# UmnitsaControl.net
KiCad netlist of a schematic drawn in EAGLE
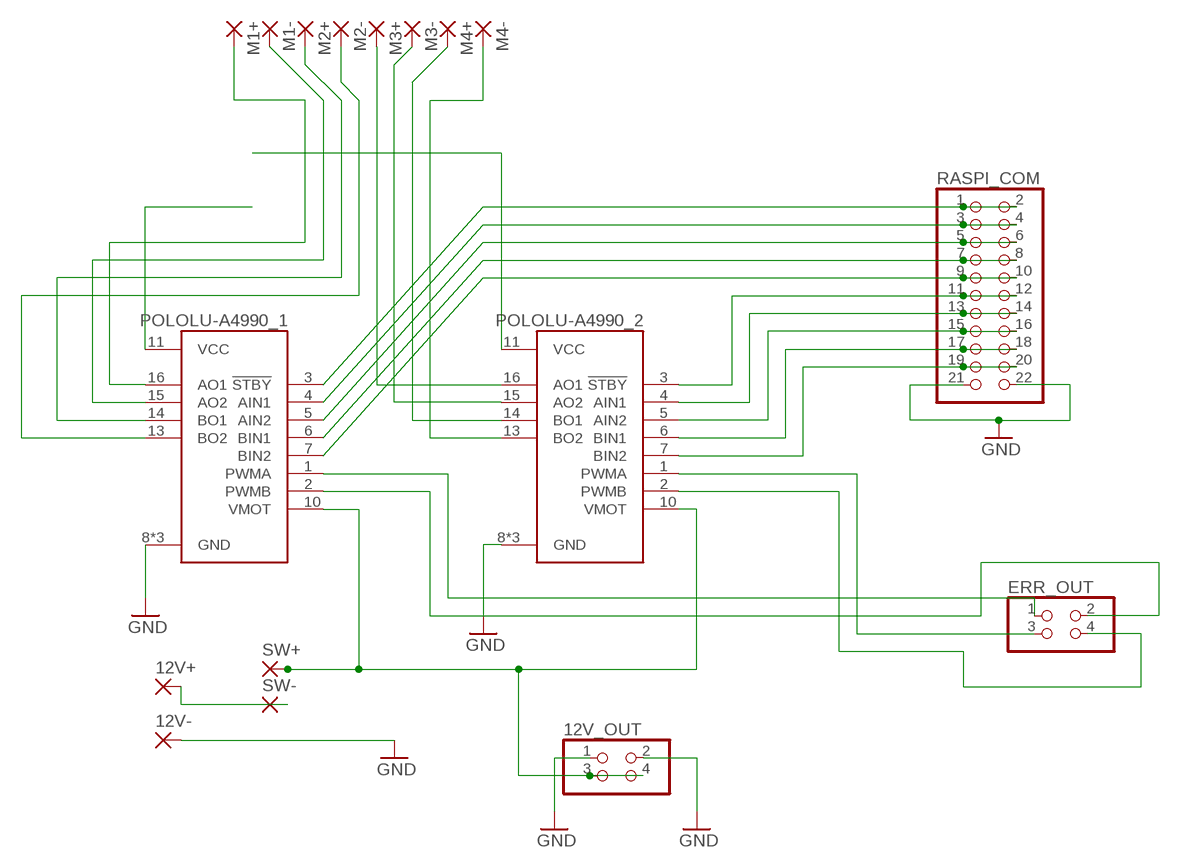
[diagram p0: schematic, sheet 1]

(export (version "E")
  (design (tool "Eeschema 10.0.6"))
  (components
    (comp (ref "12V+")
      (value "3,81/1,4")
      (footprint "eagle-import:3,81_1,4")
      (libsource (lib "eagle-import") (part "3,81/1,4"))
    )
    (comp (ref "12V-")
      (value "3,81/1,4")
      (footprint "eagle-import:3,81_1,4")
      (libsource (lib "eagle-import") (part "3,81/1,4"))
    )
    (comp (ref "12V_OUT")
      (value "PINHD-2X2")
      (footprint "eagle-import:2X02")
      (libsource (lib "eagle-import") (part "PINHD-2X2"))
    )
    (comp (ref "ERR_OUT")
      (value "PINHD-2X2")
      (footprint "eagle-import:2X02")
      (libsource (lib "eagle-import") (part "PINHD-2X2"))
    )
    (comp (ref "M1+")
      (value "3,81/1,4")
      (footprint "eagle-import:3,81_1,4")
      (libsource (lib "eagle-import") (part "3,81/1,4"))
    )
    (comp (ref "M1-")
      (value "3,81/1,4")
      (footprint "eagle-import:3,81_1,4")
      (libsource (lib "eagle-import") (part "3,81/1,4"))
    )
    (comp (ref "M2+")
      (value "3,81/1,4")
      (footprint "eagle-import:3,81_1,4")
      (libsource (lib "eagle-import") (part "3,81/1,4"))
    )
    (comp (ref "M2-")
      (value "3,81/1,4")
      (footprint "eagle-import:3,81_1,4")
      (libsource (lib "eagle-import") (part "3,81/1,4"))
    )
    (comp (ref "M3+")
      (value "3,81/1,4")
      (footprint "eagle-import:3,81_1,4")
      (libsource (lib "eagle-import") (part "3,81/1,4"))
    )
    (comp (ref "M3-")
      (value "3,81/1,4")
      (footprint "eagle-import:3,81_1,4")
      (libsource (lib "eagle-import") (part "3,81/1,4"))
    )
    (comp (ref "M4+")
      (value "3,81/1,4")
      (footprint "eagle-import:3,81_1,4")
      (libsource (lib "eagle-import") (part "3,81/1,4"))
    )
    (comp (ref "M4-")
      (value "3,81/1,4")
      (footprint "eagle-import:3,81_1,4")
      (libsource (lib "eagle-import") (part "3,81/1,4"))
    )
    (comp (ref "POLOLU-A4990_1")
      (value "POLOLU-713")
      (footprint "eagle-import:SHIELD_POLOLU-713")
      (fields (field (name "MF") "Pololu"))
      (libsource (lib "eagle-import") (part "POLOLU-713"))
    )
    (comp (ref "POLOLU-A4990_2")
      (value "POLOLU-713")
      (footprint "eagle-import:SHIELD_POLOLU-713")
      (fields (field (name "MF") "Pololu"))
      (libsource (lib "eagle-import") (part "POLOLU-713"))
    )
    (comp (ref "RASPI_COM")
      (value "PINHD-2X11")
      (footprint "eagle-import:2X11")
      (libsource (lib "eagle-import") (part "PINHD-2X11"))
    )
    (comp (ref "SW+")
      (value "2,54/1,0")
      (footprint "eagle-import:2,54_1,0")
      (libsource (lib "eagle-import") (part "2,54/1,0"))
    )
    (comp (ref "SW-")
      (value "2,54/1,0")
      (footprint "eagle-import:2,54_1,0")
      (libsource (lib "eagle-import") (part "2,54/1,0"))
    )
  )
  (nets
    (net (code "1") (name "GND") (class "Default")
      (node (ref "12V-") (pin "1") (pinfunction "P_1") (pintype "passive"))
      (node (ref "12V_OUT") (pin "1") (pinfunction "1_1") (pintype "passive"))
      (node (ref "12V_OUT") (pin "2") (pinfunction "2_2") (pintype "passive"))
      (node (ref "POLOLU-A4990_1") (pin "12") (pinfunction "GND_12") (pintype "power_in"))
      (node (ref "POLOLU-A4990_1") (pin "8") (pinfunction "GND_8") (pintype "power_in"))
      (node (ref "POLOLU-A4990_1") (pin "9") (pinfunction "GND_9") (pintype "power_in"))
      (node (ref "POLOLU-A4990_2") (pin "12") (pinfunction "GND_12") (pintype "power_in"))
      (node (ref "POLOLU-A4990_2") (pin "8") (pinfunction "GND_8") (pintype "power_in"))
      (node (ref "POLOLU-A4990_2") (pin "9") (pinfunction "GND_9") (pintype "power_in"))
      (node (ref "RASPI_COM") (pin "21") (pinfunction "21_21") (pintype "passive"))
      (node (ref "RASPI_COM") (pin "22") (pinfunction "22_22") (pintype "passive"))
    )
    (net (code "2") (name "Net-(12V+-P)") (class "Default")
      (node (ref "12V+") (pin "1") (pinfunction "P_1") (pintype "passive"))
      (node (ref "SW-") (pin "1") (pinfunction "P_1") (pintype "passive"))
    )
    (net (code "3") (name "Net-(M1+-P)") (class "Default")
      (node (ref "M1+") (pin "1") (pinfunction "P_1") (pintype "passive"))
      (node (ref "POLOLU-A4990_1") (pin "16") (pinfunction "AO1_16") (pintype "output"))
    )
    (net (code "4") (name "Net-(M1--P)") (class "Default")
      (node (ref "M1-") (pin "1") (pinfunction "P_1") (pintype "passive"))
      (node (ref "POLOLU-A4990_1") (pin "15") (pinfunction "AO2_15") (pintype "output"))
    )
    (net (code "5") (name "Net-(M2+-P)") (class "Default")
      (node (ref "M2+") (pin "1") (pinfunction "P_1") (pintype "passive"))
      (node (ref "POLOLU-A4990_1") (pin "14") (pinfunction "BO1_14") (pintype "output"))
    )
    (net (code "6") (name "Net-(M2--P)") (class "Default")
      (node (ref "M2-") (pin "1") (pinfunction "P_1") (pintype "passive"))
      (node (ref "POLOLU-A4990_1") (pin "13") (pinfunction "BO2_13") (pintype "output"))
    )
    (net (code "7") (name "Net-(M3+-P)") (class "Default")
      (node (ref "M3+") (pin "1") (pinfunction "P_1") (pintype "passive"))
      (node (ref "POLOLU-A4990_2") (pin "16") (pinfunction "AO1_16") (pintype "output"))
    )
    (net (code "8") (name "Net-(M3--P)") (class "Default")
      (node (ref "M3-") (pin "1") (pinfunction "P_1") (pintype "passive"))
      (node (ref "POLOLU-A4990_2") (pin "15") (pinfunction "AO2_15") (pintype "output"))
    )
    (net (code "9") (name "Net-(M4+-P)") (class "Default")
      (node (ref "M4+") (pin "1") (pinfunction "P_1") (pintype "passive"))
      (node (ref "POLOLU-A4990_2") (pin "14") (pinfunction "BO1_14") (pintype "output"))
    )
    (net (code "10") (name "Net-(M4--P)") (class "Default")
      (node (ref "M4-") (pin "1") (pinfunction "P_1") (pintype "passive"))
      (node (ref "POLOLU-A4990_2") (pin "13") (pinfunction "BO2_13") (pintype "output"))
    )
    (net (code "11") (name "Net-(POLOLU-A4990_1-AIN1)") (class "Default")
      (node (ref "POLOLU-A4990_1") (pin "4") (pinfunction "AIN1_4") (pintype "input"))
      (node (ref "RASPI_COM") (pin "3") (pinfunction "3_3") (pintype "passive"))
      (node (ref "RASPI_COM") (pin "4") (pinfunction "4_4") (pintype "passive"))
    )
    (net (code "12") (name "Net-(POLOLU-A4990_1-AIN2)") (class "Default")
      (node (ref "POLOLU-A4990_1") (pin "5") (pinfunction "AIN2_5") (pintype "input"))
      (node (ref "RASPI_COM") (pin "5") (pinfunction "5_5") (pintype "passive"))
      (node (ref "RASPI_COM") (pin "6") (pinfunction "6_6") (pintype "passive"))
    )
    (net (code "13") (name "Net-(POLOLU-A4990_1-BIN1)") (class "Default")
      (node (ref "POLOLU-A4990_1") (pin "6") (pinfunction "BIN1_6") (pintype "input"))
      (node (ref "RASPI_COM") (pin "7") (pinfunction "7_7") (pintype "passive"))
      (node (ref "RASPI_COM") (pin "8") (pinfunction "8_8") (pintype "passive"))
    )
    (net (code "14") (name "Net-(POLOLU-A4990_1-BIN2)") (class "Default")
      (node (ref "POLOLU-A4990_1") (pin "7") (pinfunction "BIN2_7") (pintype "input"))
      (node (ref "RASPI_COM") (pin "10") (pinfunction "10_10") (pintype "passive"))
      (node (ref "RASPI_COM") (pin "9") (pinfunction "9_9") (pintype "passive"))
    )
    (net (code "15") (name "Net-(POLOLU-A4990_1-PWMA)") (class "Default")
      (node (ref "ERR_OUT") (pin "1") (pinfunction "1_1") (pintype "passive"))
      (node (ref "POLOLU-A4990_1") (pin "1") (pinfunction "PWMA_1") (pintype "input"))
    )
    (net (code "16") (name "Net-(POLOLU-A4990_1-PWMB)") (class "Default")
      (node (ref "ERR_OUT") (pin "2") (pinfunction "2_2") (pintype "passive"))
      (node (ref "POLOLU-A4990_1") (pin "2") (pinfunction "PWMB_2") (pintype "input"))
    )
    (net (code "17") (name "Net-(POLOLU-A4990_1-VMOT)") (class "Default")
      (node (ref "12V_OUT") (pin "3") (pinfunction "3_3") (pintype "passive"))
      (node (ref "12V_OUT") (pin "4") (pinfunction "4_4") (pintype "passive"))
      (node (ref "POLOLU-A4990_1") (pin "10") (pinfunction "VMOT_10") (pintype "input"))
      (node (ref "POLOLU-A4990_2") (pin "10") (pinfunction "VMOT_10") (pintype "input"))
      (node (ref "SW+") (pin "1") (pinfunction "P_1") (pintype "passive"))
    )
    (net (code "18") (name "Net-(POLOLU-A4990_1-~{STBY})") (class "Default")
      (node (ref "POLOLU-A4990_1") (pin "3") (pinfunction "~{STBY}_3") (pintype "input"))
      (node (ref "RASPI_COM") (pin "1") (pinfunction "1_1") (pintype "passive"))
      (node (ref "RASPI_COM") (pin "2") (pinfunction "2_2") (pintype "passive"))
    )
    (net (code "19") (name "Net-(POLOLU-A4990_2-AIN1)") (class "Default")
      (node (ref "POLOLU-A4990_2") (pin "4") (pinfunction "AIN1_4") (pintype "input"))
      (node (ref "RASPI_COM") (pin "13") (pinfunction "13_13") (pintype "passive"))
      (node (ref "RASPI_COM") (pin "14") (pinfunction "14_14") (pintype "passive"))
    )
    (net (code "20") (name "Net-(POLOLU-A4990_2-AIN2)") (class "Default")
      (node (ref "POLOLU-A4990_2") (pin "5") (pinfunction "AIN2_5") (pintype "input"))
      (node (ref "RASPI_COM") (pin "15") (pinfunction "15_15") (pintype "passive"))
      (node (ref "RASPI_COM") (pin "16") (pinfunction "16_16") (pintype "passive"))
    )
    (net (code "21") (name "Net-(POLOLU-A4990_2-BIN1)") (class "Default")
      (node (ref "POLOLU-A4990_2") (pin "6") (pinfunction "BIN1_6") (pintype "input"))
      (node (ref "RASPI_COM") (pin "17") (pinfunction "17_17") (pintype "passive"))
      (node (ref "RASPI_COM") (pin "18") (pinfunction "18_18") (pintype "passive"))
    )
    (net (code "22") (name "Net-(POLOLU-A4990_2-BIN2)") (class "Default")
      (node (ref "POLOLU-A4990_2") (pin "7") (pinfunction "BIN2_7") (pintype "input"))
      (node (ref "RASPI_COM") (pin "19") (pinfunction "19_19") (pintype "passive"))
      (node (ref "RASPI_COM") (pin "20") (pinfunction "20_20") (pintype "passive"))
    )
    (net (code "23") (name "Net-(POLOLU-A4990_2-PWMA)") (class "Default")
      (node (ref "ERR_OUT") (pin "3") (pinfunction "3_3") (pintype "passive"))
      (node (ref "POLOLU-A4990_2") (pin "1") (pinfunction "PWMA_1") (pintype "input"))
    )
    (net (code "24") (name "Net-(POLOLU-A4990_2-PWMB)") (class "Default")
      (node (ref "ERR_OUT") (pin "4") (pinfunction "4_4") (pintype "passive"))
      (node (ref "POLOLU-A4990_2") (pin "2") (pinfunction "PWMB_2") (pintype "input"))
    )
    (net (code "25") (name "Net-(POLOLU-A4990_2-~{STBY})") (class "Default")
      (node (ref "POLOLU-A4990_2") (pin "3") (pinfunction "~{STBY}_3") (pintype "input"))
      (node (ref "RASPI_COM") (pin "11") (pinfunction "11_11") (pintype "passive"))
      (node (ref "RASPI_COM") (pin "12") (pinfunction "12_12") (pintype "passive"))
    )
    (net (code "26") (name "unconnected-(POLOLU-A4990_1-VCC-Pad11)") (class "Default")
      (node (ref "POLOLU-A4990_1") (pin "11") (pinfunction "VCC_11") (pintype "power_in"))
    )
    (net (code "27") (name "unconnected-(POLOLU-A4990_2-VCC-Pad11)") (class "Default")
      (node (ref "POLOLU-A4990_2") (pin "11") (pinfunction "VCC_11") (pintype "power_in"))
    )
  )
)
